# ASCII_09_FPGA_banks_5_6_7_8.net
KiCad netlist of a schematic drawn in Altium Designer
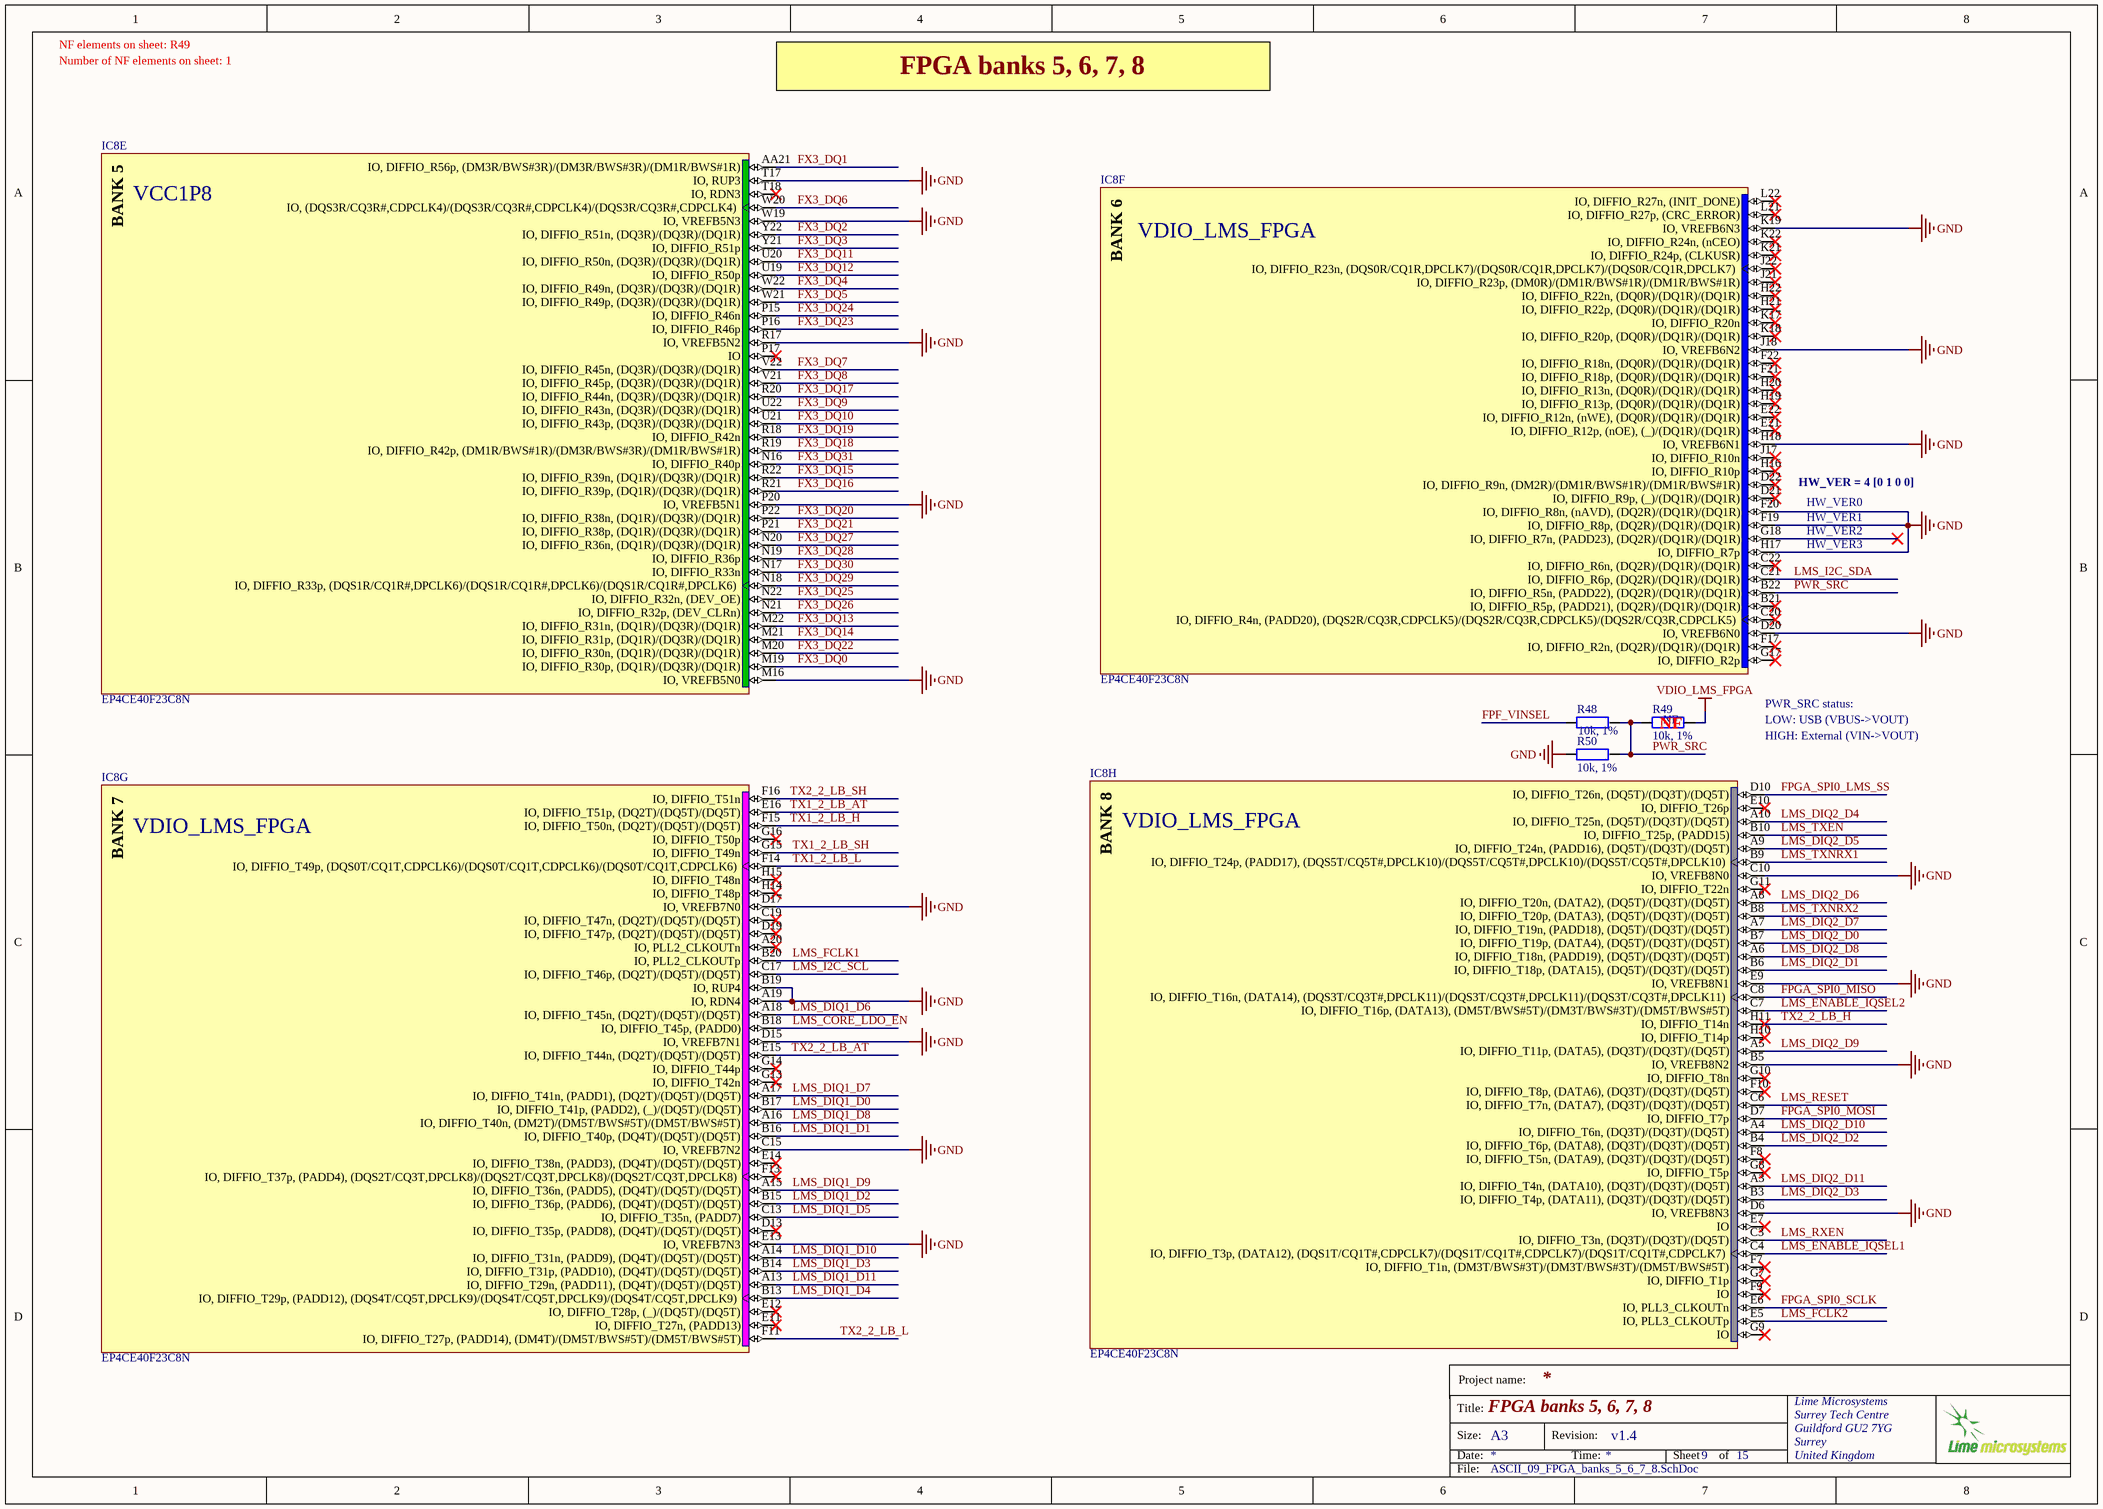
[diagram p0: ASCII_09_FPGA_banks_5_6_7_8.SchDoc]

(export (version "E")
  (design (tool "Eeschema 10.0.6"))
  (components
    (comp (ref "IC8")
      (value "EP4CE40F23C8N")
      (footprint "FBGA484_A-240")
      (description "IC FPGA 328 I/O 484FBGA")
      (fields (field (name "MANUFACTURER") "Altera"))
      (libsource (lib "LimeMicroAltiumLib_schLib") (part "EP4CE40F23C7N"))
    )
    (comp (ref "R48")
      (value "10k, 1%")
      (footprint "RES0402")
      (fields (field (name "MANUFACTURER") "Yageo") (field (name "TOLERANCE") "±1%"))
      (libsource (lib "LimeMicroAltiumLib_schLib") (part "Res_0402"))
    )
    (comp (ref "R49")
      (value "10k, 1%")
      (footprint "RES0402")
      (fields
        (field (name "ASSEMBLY INFO") "NF")
        (field (name "MANUFACTURER") "Yageo")
        (field (name "TOLERANCE") "±1%")
      )
      (libsource (lib "LimeMicroAltiumLib_schLib") (part "Res_0402"))
    )
    (comp (ref "R50")
      (value "10k, 1%")
      (footprint "RES0402")
      (fields (field (name "MANUFACTURER") "Yageo") (field (name "TOLERANCE") "±1%"))
      (libsource (lib "LimeMicroAltiumLib_schLib") (part "Res_0402"))
    )
  )
  (nets
    (net (code "1") (name "/FPF_VINSEL") (class "Default")
      (node (ref "R48") (pin "1") (pinfunction "1_1") (pintype "passive"))
    )
    (net (code "2") (name "/FPGA_SPI0_LMS_SS") (class "Default")
      (node (ref "IC8") (pin "D10") (pinfunction "IO,_DIFFIO_T26n,_(DQ5T)/(DQ3T)/(DQ5T)_D10") (pintype "bidirectional"))
    )
    (net (code "3") (name "/FPGA_SPI0_MISO") (class "Default")
      (node (ref "IC8") (pin "C8") (pinfunction "IO,_DIFFIO_T16n,_(DATA14),_(DQS3T/CQ3T#,DPCLK11)/(DQS3T/CQ3T#,DPCLK11)/(DQS3T/CQ3T#,DPCLK11)_C8") (pintype "bidirectional"))
    )
    (net (code "4") (name "/FPGA_SPI0_MOSI") (class "Default")
      (node (ref "IC8") (pin "D7") (pinfunction "IO,_DIFFIO_T7p_D7") (pintype "bidirectional"))
    )
    (net (code "5") (name "/FPGA_SPI0_SCLK") (class "Default")
      (node (ref "IC8") (pin "E6") (pinfunction "IO,_PLL3_CLKOUTn_E6") (pintype "bidirectional"))
    )
    (net (code "6") (name "/FX3_DQ0") (class "Default")
      (node (ref "IC8") (pin "M19") (pinfunction "IO,_DIFFIO_R30p,_(DQ1R)/(DQ3R)/(DQ1R)_M19") (pintype "bidirectional"))
    )
    (net (code "7") (name "/FX3_DQ1") (class "Default")
      (node (ref "IC8") (pin "AA21") (pinfunction "IO,_DIFFIO_R56p,_(DM3R/BWS#3R)/(DM3R/BWS#3R)/(DM1R/BWS#1R)_AA21") (pintype "bidirectional"))
    )
    (net (code "8") (name "/FX3_DQ2") (class "Default")
      (node (ref "IC8") (pin "Y22") (pinfunction "IO,_DIFFIO_R51n,_(DQ3R)/(DQ3R)/(DQ1R)_Y22") (pintype "bidirectional"))
    )
    (net (code "9") (name "/FX3_DQ3") (class "Default")
      (node (ref "IC8") (pin "Y21") (pinfunction "IO,_DIFFIO_R51p_Y21") (pintype "bidirectional"))
    )
    (net (code "10") (name "/FX3_DQ4") (class "Default")
      (node (ref "IC8") (pin "W22") (pinfunction "IO,_DIFFIO_R49n,_(DQ3R)/(DQ3R)/(DQ1R)_W22") (pintype "bidirectional"))
    )
    (net (code "11") (name "/FX3_DQ5") (class "Default")
      (node (ref "IC8") (pin "W21") (pinfunction "IO,_DIFFIO_R49p,_(DQ3R)/(DQ3R)/(DQ1R)_W21") (pintype "bidirectional"))
    )
    (net (code "12") (name "/FX3_DQ6") (class "Default")
      (node (ref "IC8") (pin "W20") (pinfunction "IO,_(DQS3R/CQ3R#,CDPCLK4)/(DQS3R/CQ3R#,CDPCLK4)/(DQS3R/CQ3R#,CDPCLK4)_W20") (pintype "bidirectional"))
    )
    (net (code "13") (name "/FX3_DQ7") (class "Default")
      (node (ref "IC8") (pin "V22") (pinfunction "IO,_DIFFIO_R45n,_(DQ3R)/(DQ3R)/(DQ1R)_V22") (pintype "bidirectional"))
    )
    (net (code "14") (name "/FX3_DQ8") (class "Default")
      (node (ref "IC8") (pin "V21") (pinfunction "IO,_DIFFIO_R45p,_(DQ3R)/(DQ3R)/(DQ1R)_V21") (pintype "bidirectional"))
    )
    (net (code "15") (name "/FX3_DQ9") (class "Default")
      (node (ref "IC8") (pin "U22") (pinfunction "IO,_DIFFIO_R43n,_(DQ3R)/(DQ3R)/(DQ1R)_U22") (pintype "bidirectional"))
    )
    (net (code "16") (name "/FX3_DQ10") (class "Default")
      (node (ref "IC8") (pin "U21") (pinfunction "IO,_DIFFIO_R43p,_(DQ3R)/(DQ3R)/(DQ1R)_U21") (pintype "bidirectional"))
    )
    (net (code "17") (name "/FX3_DQ11") (class "Default")
      (node (ref "IC8") (pin "U20") (pinfunction "IO,_DIFFIO_R50n,_(DQ3R)/(DQ3R)/(DQ1R)_U20") (pintype "bidirectional"))
    )
    (net (code "18") (name "/FX3_DQ12") (class "Default")
      (node (ref "IC8") (pin "U19") (pinfunction "IO,_DIFFIO_R50p_U19") (pintype "bidirectional"))
    )
    (net (code "19") (name "/FX3_DQ13") (class "Default")
      (node (ref "IC8") (pin "M22") (pinfunction "IO,_DIFFIO_R31n,_(DQ1R)/(DQ3R)/(DQ1R)_M22") (pintype "bidirectional"))
    )
    (net (code "20") (name "/FX3_DQ14") (class "Default")
      (node (ref "IC8") (pin "M21") (pinfunction "IO,_DIFFIO_R31p,_(DQ1R)/(DQ3R)/(DQ1R)_M21") (pintype "bidirectional"))
    )
    (net (code "21") (name "/FX3_DQ15") (class "Default")
      (node (ref "IC8") (pin "R22") (pinfunction "IO,_DIFFIO_R39n,_(DQ1R)/(DQ3R)/(DQ1R)_R22") (pintype "bidirectional"))
    )
    (net (code "22") (name "/FX3_DQ16") (class "Default")
      (node (ref "IC8") (pin "R21") (pinfunction "IO,_DIFFIO_R39p,_(DQ1R)/(DQ3R)/(DQ1R)_R21") (pintype "bidirectional"))
    )
    (net (code "23") (name "/FX3_DQ17") (class "Default")
      (node (ref "IC8") (pin "R20") (pinfunction "IO,_DIFFIO_R44n,_(DQ3R)/(DQ3R)/(DQ1R)_R20") (pintype "bidirectional"))
    )
    (net (code "24") (name "/FX3_DQ18") (class "Default")
      (node (ref "IC8") (pin "R19") (pinfunction "IO,_DIFFIO_R42p,_(DM1R/BWS#1R)/(DM3R/BWS#3R)/(DM1R/BWS#1R)_R19") (pintype "bidirectional"))
    )
    (net (code "25") (name "/FX3_DQ19") (class "Default")
      (node (ref "IC8") (pin "R18") (pinfunction "IO,_DIFFIO_R42n_R18") (pintype "bidirectional"))
    )
    (net (code "26") (name "/FX3_DQ20") (class "Default")
      (node (ref "IC8") (pin "P22") (pinfunction "IO,_DIFFIO_R38n,_(DQ1R)/(DQ3R)/(DQ1R)_P22") (pintype "bidirectional"))
    )
    (net (code "27") (name "/FX3_DQ21") (class "Default")
      (node (ref "IC8") (pin "P21") (pinfunction "IO,_DIFFIO_R38p,_(DQ1R)/(DQ3R)/(DQ1R)_P21") (pintype "bidirectional"))
    )
    (net (code "28") (name "/FX3_DQ22") (class "Default")
      (node (ref "IC8") (pin "M20") (pinfunction "IO,_DIFFIO_R30n,_(DQ1R)/(DQ3R)/(DQ1R)_M20") (pintype "bidirectional"))
    )
    (net (code "29") (name "/FX3_DQ23") (class "Default")
      (node (ref "IC8") (pin "P16") (pinfunction "IO,_DIFFIO_R46p_P16") (pintype "bidirectional"))
    )
    (net (code "30") (name "/FX3_DQ24") (class "Default")
      (node (ref "IC8") (pin "P15") (pinfunction "IO,_DIFFIO_R46n_P15") (pintype "bidirectional"))
    )
    (net (code "31") (name "/FX3_DQ25") (class "Default")
      (node (ref "IC8") (pin "N22") (pinfunction "IO,_DIFFIO_R32n,_(DEV_OE)_N22") (pintype "bidirectional"))
    )
    (net (code "32") (name "/FX3_DQ26") (class "Default")
      (node (ref "IC8") (pin "N21") (pinfunction "IO,_DIFFIO_R32p,_(DEV_CLRn)_N21") (pintype "bidirectional"))
    )
    (net (code "33") (name "/FX3_DQ27") (class "Default")
      (node (ref "IC8") (pin "N20") (pinfunction "IO,_DIFFIO_R36n,_(DQ1R)/(DQ3R)/(DQ1R)_N20") (pintype "bidirectional"))
    )
    (net (code "34") (name "/FX3_DQ28") (class "Default")
      (node (ref "IC8") (pin "N19") (pinfunction "IO,_DIFFIO_R36p_N19") (pintype "bidirectional"))
    )
    (net (code "35") (name "/FX3_DQ29") (class "Default")
      (node (ref "IC8") (pin "N18") (pinfunction "IO,_DIFFIO_R33p,_(DQS1R/CQ1R#,DPCLK6)/(DQS1R/CQ1R#,DPCLK6)/(DQS1R/CQ1R#,DPCLK6)_N18") (pintype "bidirectional"))
    )
    (net (code "36") (name "/FX3_DQ30") (class "Default")
      (node (ref "IC8") (pin "N17") (pinfunction "IO,_DIFFIO_R33n_N17") (pintype "bidirectional"))
    )
    (net (code "37") (name "/FX3_DQ31") (class "Default")
      (node (ref "IC8") (pin "N16") (pinfunction "IO,_DIFFIO_R40p_N16") (pintype "bidirectional"))
    )
    (net (code "38") (name "/LMS_CORE_LDO_EN") (class "Default")
      (node (ref "IC8") (pin "B18") (pinfunction "IO,_DIFFIO_T45p,_(PADD0)_B18") (pintype "bidirectional"))
    )
    (net (code "39") (name "/LMS_DIQ1_D0") (class "Default")
      (node (ref "IC8") (pin "B17") (pinfunction "IO,_DIFFIO_T41p,_(PADD2),_(_)/(DQ5T)/(DQ5T)_B17") (pintype "bidirectional"))
    )
    (net (code "40") (name "/LMS_DIQ1_D1") (class "Default")
      (node (ref "IC8") (pin "B16") (pinfunction "IO,_DIFFIO_T40p,_(DQ4T)/(DQ5T)/(DQ5T)_B16") (pintype "bidirectional"))
    )
    (net (code "41") (name "/LMS_DIQ1_D2") (class "Default")
      (node (ref "IC8") (pin "B15") (pinfunction "IO,_DIFFIO_T36p,_(PADD6),_(DQ4T)/(DQ5T)/(DQ5T)_B15") (pintype "bidirectional"))
    )
    (net (code "42") (name "/LMS_DIQ1_D3") (class "Default")
      (node (ref "IC8") (pin "B14") (pinfunction "IO,_DIFFIO_T31p,_(PADD10),_(DQ4T)/(DQ5T)/(DQ5T)_B14") (pintype "bidirectional"))
    )
    (net (code "43") (name "/LMS_DIQ1_D4") (class "Default")
      (node (ref "IC8") (pin "B13") (pinfunction "IO,_DIFFIO_T29p,_(PADD12),_(DQS4T/CQ5T,DPCLK9)/(DQS4T/CQ5T,DPCLK9)/(DQS4T/CQ5T,DPCLK9)_B13") (pintype "bidirectional"))
    )
    (net (code "44") (name "/LMS_DIQ1_D5") (class "Default")
      (node (ref "IC8") (pin "C13") (pinfunction "IO,_DIFFIO_T35n,_(PADD7)_C13") (pintype "bidirectional"))
    )
    (net (code "45") (name "/LMS_DIQ1_D6") (class "Default")
      (node (ref "IC8") (pin "A18") (pinfunction "IO,_DIFFIO_T45n,_(DQ2T)/(DQ5T)/(DQ5T)_A18") (pintype "bidirectional"))
    )
    (net (code "46") (name "/LMS_DIQ1_D7") (class "Default")
      (node (ref "IC8") (pin "A17") (pinfunction "IO,_DIFFIO_T41n,_(PADD1),_(DQ2T)/(DQ5T)/(DQ5T)_A17") (pintype "bidirectional"))
    )
    (net (code "47") (name "/LMS_DIQ1_D8") (class "Default")
      (node (ref "IC8") (pin "A16") (pinfunction "IO,_DIFFIO_T40n,_(DM2T)/(DM5T/BWS#5T)/(DM5T/BWS#5T)_A16") (pintype "bidirectional"))
    )
    (net (code "48") (name "/LMS_DIQ1_D9") (class "Default")
      (node (ref "IC8") (pin "A15") (pinfunction "IO,_DIFFIO_T36n,_(PADD5),_(DQ4T)/(DQ5T)/(DQ5T)_A15") (pintype "bidirectional"))
    )
    (net (code "49") (name "/LMS_DIQ1_D10") (class "Default")
      (node (ref "IC8") (pin "A14") (pinfunction "IO,_DIFFIO_T31n,_(PADD9),_(DQ4T)/(DQ5T)/(DQ5T)_A14") (pintype "bidirectional"))
    )
    (net (code "50") (name "/LMS_DIQ1_D11") (class "Default")
      (node (ref "IC8") (pin "A13") (pinfunction "IO,_DIFFIO_T29n,_(PADD11),_(DQ4T)/(DQ5T)/(DQ5T)_A13") (pintype "bidirectional"))
    )
    (net (code "51") (name "/LMS_DIQ2_D0") (class "Default")
      (node (ref "IC8") (pin "B7") (pinfunction "IO,_DIFFIO_T19p,_(DATA4),_(DQ5T)/(DQ3T)/(DQ5T)_B7") (pintype "bidirectional"))
    )
    (net (code "52") (name "/LMS_DIQ2_D1") (class "Default")
      (node (ref "IC8") (pin "B6") (pinfunction "IO,_DIFFIO_T18p,_(DATA15),_(DQ5T)/(DQ3T)/(DQ5T)_B6") (pintype "bidirectional"))
    )
    (net (code "53") (name "/LMS_DIQ2_D2") (class "Default")
      (node (ref "IC8") (pin "B4") (pinfunction "IO,_DIFFIO_T6p,_(DATA8),_(DQ3T)/(DQ3T)/(DQ5T)_B4") (pintype "bidirectional"))
    )
    (net (code "54") (name "/LMS_DIQ2_D3") (class "Default")
      (node (ref "IC8") (pin "B3") (pinfunction "IO,_DIFFIO_T4p,_(DATA11),_(DQ3T)/(DQ3T)/(DQ5T)_B3") (pintype "bidirectional"))
    )
    (net (code "55") (name "/LMS_DIQ2_D4") (class "Default")
      (node (ref "IC8") (pin "A10") (pinfunction "IO,_DIFFIO_T25n,_(DQ5T)/(DQ3T)/(DQ5T)_A10") (pintype "bidirectional"))
    )
    (net (code "56") (name "/LMS_DIQ2_D5") (class "Default")
      (node (ref "IC8") (pin "A9") (pinfunction "IO,_DIFFIO_T24n,_(PADD16),_(DQ5T)/(DQ3T)/(DQ5T)_A9") (pintype "bidirectional"))
    )
    (net (code "57") (name "/LMS_DIQ2_D6") (class "Default")
      (node (ref "IC8") (pin "A8") (pinfunction "IO,_DIFFIO_T20n,_(DATA2),_(DQ5T)/(DQ3T)/(DQ5T)_A8") (pintype "bidirectional"))
    )
    (net (code "58") (name "/LMS_DIQ2_D7") (class "Default")
      (node (ref "IC8") (pin "A7") (pinfunction "IO,_DIFFIO_T19n,_(PADD18),_(DQ5T)/(DQ3T)/(DQ5T)_A7") (pintype "bidirectional"))
    )
    (net (code "59") (name "/LMS_DIQ2_D8") (class "Default")
      (node (ref "IC8") (pin "A6") (pinfunction "IO,_DIFFIO_T18n,_(PADD19),_(DQ5T)/(DQ3T)/(DQ5T)_A6") (pintype "bidirectional"))
    )
    (net (code "60") (name "/LMS_DIQ2_D9") (class "Default")
      (node (ref "IC8") (pin "A5") (pinfunction "IO,_DIFFIO_T11p,_(DATA5),_(DQ3T)/(DQ3T)/(DQ5T)_A5") (pintype "bidirectional"))
    )
    (net (code "61") (name "/LMS_DIQ2_D10") (class "Default")
      (node (ref "IC8") (pin "A4") (pinfunction "IO,_DIFFIO_T6n,_(DQ3T)/(DQ3T)/(DQ5T)_A4") (pintype "bidirectional"))
    )
    (net (code "62") (name "/LMS_DIQ2_D11") (class "Default")
      (node (ref "IC8") (pin "A3") (pinfunction "IO,_DIFFIO_T4n,_(DATA10),_(DQ3T)/(DQ3T)/(DQ5T)_A3") (pintype "bidirectional"))
    )
    (net (code "63") (name "/LMS_ENABLE_IQSEL1") (class "Default")
      (node (ref "IC8") (pin "C4") (pinfunction "IO,_DIFFIO_T3p,_(DATA12),_(DQS1T/CQ1T#,CDPCLK7)/(DQS1T/CQ1T#,CDPCLK7)/(DQS1T/CQ1T#,CDPCLK7)_C4") (pintype "bidirectional"))
    )
    (net (code "64") (name "/LMS_ENABLE_IQSEL2") (class "Default")
      (node (ref "IC8") (pin "C7") (pinfunction "IO,_DIFFIO_T16p,_(DATA13),_(DM5T/BWS#5T)/(DM3T/BWS#3T)/(DM5T/BWS#5T)_C7") (pintype "bidirectional"))
    )
    (net (code "65") (name "/LMS_FCLK1") (class "Default")
      (node (ref "IC8") (pin "B20") (pinfunction "IO,_PLL2_CLKOUTp_B20") (pintype "bidirectional"))
    )
    (net (code "66") (name "/LMS_FCLK2") (class "Default")
      (node (ref "IC8") (pin "E5") (pinfunction "IO,_PLL3_CLKOUTp_E5") (pintype "bidirectional"))
    )
    (net (code "67") (name "/LMS_I2C_SCL") (class "Default")
      (node (ref "IC8") (pin "C17") (pinfunction "IO,_DIFFIO_T46p,_(DQ2T)/(DQ5T)/(DQ5T)_C17") (pintype "bidirectional"))
    )
    (net (code "68") (name "/LMS_I2C_SDA") (class "Default")
      (node (ref "IC8") (pin "C21") (pinfunction "IO,_DIFFIO_R6p,_(DQ2R)/(DQ1R)/(DQ1R)_C21") (pintype "bidirectional"))
    )
    (net (code "69") (name "/LMS_RESET") (class "Default")
      (node (ref "IC8") (pin "C6") (pinfunction "IO,_DIFFIO_T7n,_(DATA7),_(DQ3T)/(DQ3T)/(DQ5T)_C6") (pintype "bidirectional"))
    )
    (net (code "70") (name "/LMS_RXEN") (class "Default")
      (node (ref "IC8") (pin "C3") (pinfunction "IO,_DIFFIO_T3n,_(DQ3T)/(DQ3T)/(DQ5T)_C3") (pintype "bidirectional"))
    )
    (net (code "71") (name "/LMS_TXEN") (class "Default")
      (node (ref "IC8") (pin "B10") (pinfunction "IO,_DIFFIO_T25p,_(PADD15)_B10") (pintype "bidirectional"))
    )
    (net (code "72") (name "/LMS_TXNRX1") (class "Default")
      (node (ref "IC8") (pin "B9") (pinfunction "IO,_DIFFIO_T24p,_(PADD17),_(DQS5T/CQ5T#,DPCLK10)/(DQS5T/CQ5T#,DPCLK10)/(DQS5T/CQ5T#,DPCLK10)_B9") (pintype "bidirectional"))
    )
    (net (code "73") (name "/LMS_TXNRX2") (class "Default")
      (node (ref "IC8") (pin "B8") (pinfunction "IO,_DIFFIO_T20p,_(DATA3),_(DQ5T)/(DQ3T)/(DQ5T)_B8") (pintype "bidirectional"))
    )
    (net (code "74") (name "/PWR_SRC") (class "Default")
      (node (ref "IC8") (pin "B22") (pinfunction "IO,_DIFFIO_R5n,_(PADD22),_(DQ2R)/(DQ1R)/(DQ1R)_B22") (pintype "bidirectional"))
      (node (ref "R48") (pin "2") (pinfunction "2_2") (pintype "passive"))
      (node (ref "R49") (pin "1") (pinfunction "1_1") (pintype "passive"))
      (node (ref "R50") (pin "2") (pinfunction "2_2") (pintype "passive"))
    )
    (net (code "75") (name "/TX1_2_LB_AT") (class "Default")
      (node (ref "IC8") (pin "E16") (pinfunction "IO,_DIFFIO_T51p,_(DQ2T)/(DQ5T)/(DQ5T)_E16") (pintype "bidirectional"))
    )
    (net (code "76") (name "/TX1_2_LB_H") (class "Default")
      (node (ref "IC8") (pin "F15") (pinfunction "IO,_DIFFIO_T50n,_(DQ2T)/(DQ5T)/(DQ5T)_F15") (pintype "bidirectional"))
    )
    (net (code "77") (name "/TX1_2_LB_L") (class "Default")
      (node (ref "IC8") (pin "F14") (pinfunction "IO,_DIFFIO_T49p,_(DQS0T/CQ1T,CDPCLK6)/(DQS0T/CQ1T,CDPCLK6)/(DQS0T/CQ1T,CDPCLK6)_F14") (pintype "bidirectional"))
    )
    (net (code "78") (name "/TX1_2_LB_SH") (class "Default")
      (node (ref "IC8") (pin "G15") (pinfunction "IO,_DIFFIO_T49n_G15") (pintype "bidirectional"))
    )
    (net (code "79") (name "/TX2_2_LB_AT") (class "Default")
      (node (ref "IC8") (pin "E15") (pinfunction "IO,_DIFFIO_T44n,_(DQ2T)/(DQ5T)/(DQ5T)_E15") (pintype "bidirectional"))
    )
    (net (code "80") (name "/TX2_2_LB_H") (class "Default")
      (node (ref "IC8") (pin "H11") (pinfunction "IO,_DIFFIO_T14n_H11") (pintype "bidirectional+no_connect"))
    )
    (net (code "81") (name "/TX2_2_LB_L") (class "Default")
      (node (ref "IC8") (pin "F11") (pinfunction "IO,_DIFFIO_T27p,_(PADD14),_(DM4T)/(DM5T/BWS#5T)/(DM5T/BWS#5T)_F11") (pintype "bidirectional"))
    )
    (net (code "82") (name "/TX2_2_LB_SH") (class "Default")
      (node (ref "IC8") (pin "F16") (pinfunction "IO,_DIFFIO_T51n_F16") (pintype "bidirectional"))
    )
    (net (code "83") (name "GND") (class "Default")
      (node (ref "IC8") (pin "A19") (pinfunction "IO,_RDN4_A19") (pintype "bidirectional"))
      (node (ref "IC8") (pin "B19") (pinfunction "IO,_RUP4_B19") (pintype "bidirectional"))
      (node (ref "IC8") (pin "B5") (pinfunction "IO,_VREFB8N2_B5") (pintype "bidirectional"))
      (node (ref "IC8") (pin "C10") (pinfunction "IO,_VREFB8N0_C10") (pintype "bidirectional"))
      (node (ref "IC8") (pin "C15") (pinfunction "IO,_VREFB7N2_C15") (pintype "bidirectional"))
      (node (ref "IC8") (pin "D15") (pinfunction "IO,_VREFB7N1_D15") (pintype "bidirectional"))
      (node (ref "IC8") (pin "D17") (pinfunction "IO,_VREFB7N0_D17") (pintype "bidirectional"))
      (node (ref "IC8") (pin "D20") (pinfunction "IO,_VREFB6N0_D20") (pintype "bidirectional"))
      (node (ref "IC8") (pin "D6") (pinfunction "IO,_VREFB8N3_D6") (pintype "bidirectional"))
      (node (ref "IC8") (pin "E13") (pinfunction "IO,_VREFB7N3_E13") (pintype "bidirectional"))
      (node (ref "IC8") (pin "E9") (pinfunction "IO,_VREFB8N1_E9") (pintype "bidirectional"))
      (node (ref "IC8") (pin "F19") (pinfunction "IO,_DIFFIO_R8p,_(DQ2R)/(DQ1R)/(DQ1R)_F19") (pintype "bidirectional"))
      (node (ref "IC8") (pin "F20") (pinfunction "IO,_DIFFIO_R8n,_(nAVD),_(DQ2R)/(DQ1R)/(DQ1R)_F20") (pintype "bidirectional"))
      (node (ref "IC8") (pin "H17") (pinfunction "IO,_DIFFIO_R7p_H17") (pintype "bidirectional"))
      (node (ref "IC8") (pin "H18") (pinfunction "IO,_VREFB6N1_H18") (pintype "bidirectional"))
      (node (ref "IC8") (pin "J18") (pinfunction "IO,_VREFB6N2_J18") (pintype "bidirectional"))
      (node (ref "IC8") (pin "K19") (pinfunction "IO,_VREFB6N3_K19") (pintype "bidirectional"))
      (node (ref "IC8") (pin "M16") (pinfunction "IO,_VREFB5N0_M16") (pintype "bidirectional"))
      (node (ref "IC8") (pin "P20") (pinfunction "IO,_VREFB5N1_P20") (pintype "bidirectional"))
      (node (ref "IC8") (pin "R17") (pinfunction "IO,_VREFB5N2_R17") (pintype "bidirectional"))
      (node (ref "IC8") (pin "T17") (pinfunction "IO,_RUP3_T17") (pintype "bidirectional"))
      (node (ref "IC8") (pin "W19") (pinfunction "IO,_VREFB5N3_W19") (pintype "bidirectional"))
      (node (ref "R50") (pin "1") (pinfunction "1_1") (pintype "passive"))
    )
    (net (code "84") (name "VDIO_LMS_FPGA") (class "Default")
      (node (ref "R49") (pin "2") (pinfunction "2_2") (pintype "passive"))
    )
    (net (code "85") (name "unconnected-(IC8E-IO,_RDN3-PadT18)") (class "Default")
      (node (ref "IC8") (pin "T18") (pinfunction "IO,_RDN3_T18") (pintype "bidirectional+no_connect"))
    )
    (net (code "86") (name "unconnected-(IC8E-IO-PadP17)") (class "Default")
      (node (ref "IC8") (pin "P17") (pinfunction "IO_P17") (pintype "bidirectional+no_connect"))
    )
    (net (code "87") (name "unconnected-(IC8F-IO,_DIFFIO_R2n,_(DQ2R){slash}(DQ1R){slash}(DQ1R)-PadF17)") (class "Default")
      (node (ref "IC8") (pin "F17") (pinfunction "IO,_DIFFIO_R2n,_(DQ2R)/(DQ1R)/(DQ1R)_F17") (pintype "bidirectional+no_connect"))
    )
    (net (code "88") (name "unconnected-(IC8F-IO,_DIFFIO_R2p-PadG17)") (class "Default")
      (node (ref "IC8") (pin "G17") (pinfunction "IO,_DIFFIO_R2p_G17") (pintype "bidirectional+no_connect"))
    )
    (net (code "89") (name "unconnected-(IC8F-IO,_DIFFIO_R4n,_(PADD20),_(DQS2R{slash}CQ3R,CDPCLK5){slash}(DQS2R{slash}CQ3R,CDPCLK5){slash}(DQS2R{slash}CQ3R,CDPCLK5)-PadC20)") (class "Default")
      (node (ref "IC8") (pin "C20") (pinfunction "IO,_DIFFIO_R4n,_(PADD20),_(DQS2R/CQ3R,CDPCLK5)/(DQS2R/CQ3R,CDPCLK5)/(DQS2R/CQ3R,CDPCLK5)_C20") (pintype "bidirectional+no_connect"))
    )
    (net (code "90") (name "unconnected-(IC8F-IO,_DIFFIO_R5p,_(PADD21),_(DQ2R){slash}(DQ1R){slash}(DQ1R)-PadB21)") (class "Default")
      (node (ref "IC8") (pin "B21") (pinfunction "IO,_DIFFIO_R5p,_(PADD21),_(DQ2R)/(DQ1R)/(DQ1R)_B21") (pintype "bidirectional+no_connect"))
    )
    (net (code "91") (name "unconnected-(IC8F-IO,_DIFFIO_R6n,_(DQ2R){slash}(DQ1R){slash}(DQ1R)-PadC22)") (class "Default")
      (node (ref "IC8") (pin "C22") (pinfunction "IO,_DIFFIO_R6n,_(DQ2R)/(DQ1R)/(DQ1R)_C22") (pintype "bidirectional+no_connect"))
    )
    (net (code "92") (name "unconnected-(IC8F-IO,_DIFFIO_R7n,_(PADD23),_(DQ2R){slash}(DQ1R){slash}(DQ1R)-PadG18)") (class "Default")
      (node (ref "IC8") (pin "G18") (pinfunction "IO,_DIFFIO_R7n,_(PADD23),_(DQ2R)/(DQ1R)/(DQ1R)_G18") (pintype "bidirectional+no_connect"))
    )
    (net (code "93") (name "unconnected-(IC8F-IO,_DIFFIO_R9n,_(DM2R){slash}(DM1R{slash}BWS#1R){slash}(DM1R{slash}BWS#1R)-PadD22)") (class "Default")
      (node (ref "IC8") (pin "D22") (pinfunction "IO,_DIFFIO_R9n,_(DM2R)/(DM1R/BWS#1R)/(DM1R/BWS#1R)_D22") (pintype "bidirectional+no_connect"))
    )
    (net (code "94") (name "unconnected-(IC8F-IO,_DIFFIO_R9p,_(_){slash}(DQ1R){slash}(DQ1R)-PadD21)") (class "Default")
      (node (ref "IC8") (pin "D21") (pinfunction "IO,_DIFFIO_R9p,_(_)/(DQ1R)/(DQ1R)_D21") (pintype "bidirectional+no_connect"))
    )
    (net (code "95") (name "unconnected-(IC8F-IO,_DIFFIO_R10n-PadJ17)") (class "Default")
      (node (ref "IC8") (pin "J17") (pinfunction "IO,_DIFFIO_R10n_J17") (pintype "bidirectional+no_connect"))
    )
    (net (code "96") (name "unconnected-(IC8F-IO,_DIFFIO_R10p-PadH16)") (class "Default")
      (node (ref "IC8") (pin "H16") (pinfunction "IO,_DIFFIO_R10p_H16") (pintype "bidirectional+no_connect"))
    )
    (net (code "97") (name "unconnected-(IC8F-IO,_DIFFIO_R12n,_(nWE),_(DQ0R){slash}(DQ1R){slash}(DQ1R)-PadE22)") (class "Default")
      (node (ref "IC8") (pin "E22") (pinfunction "IO,_DIFFIO_R12n,_(nWE),_(DQ0R)/(DQ1R)/(DQ1R)_E22") (pintype "bidirectional+no_connect"))
    )
    (net (code "98") (name "unconnected-(IC8F-IO,_DIFFIO_R12p,_(nOE),_(_){slash}(DQ1R){slash}(DQ1R)-PadE21)") (class "Default")
      (node (ref "IC8") (pin "E21") (pinfunction "IO,_DIFFIO_R12p,_(nOE),_(_)/(DQ1R)/(DQ1R)_E21") (pintype "bidirectional+no_connect"))
    )
    (net (code "99") (name "unconnected-(IC8F-IO,_DIFFIO_R13n,_(DQ0R){slash}(DQ1R){slash}(DQ1R)-PadH20)") (class "Default")
      (node (ref "IC8") (pin "H20") (pinfunction "IO,_DIFFIO_R13n,_(DQ0R)/(DQ1R)/(DQ1R)_H20") (pintype "bidirectional+no_connect"))
    )
    (net (code "100") (name "unconnected-(IC8F-IO,_DIFFIO_R13p,_(DQ0R){slash}(DQ1R){slash}(DQ1R)-PadH19)") (class "Default")
      (node (ref "IC8") (pin "H19") (pinfunction "IO,_DIFFIO_R13p,_(DQ0R)/(DQ1R)/(DQ1R)_H19") (pintype "bidirectional+no_connect"))
    )
    (net (code "101") (name "unconnected-(IC8F-IO,_DIFFIO_R18n,_(DQ0R){slash}(DQ1R){slash}(DQ1R)-PadF22)") (class "Default")
      (node (ref "IC8") (pin "F22") (pinfunction "IO,_DIFFIO_R18n,_(DQ0R)/(DQ1R)/(DQ1R)_F22") (pintype "bidirectional+no_connect"))
    )
    (net (code "102") (name "unconnected-(IC8F-IO,_DIFFIO_R18p,_(DQ0R){slash}(DQ1R){slash}(DQ1R)-PadF21)") (class "Default")
      (node (ref "IC8") (pin "F21") (pinfunction "IO,_DIFFIO_R18p,_(DQ0R)/(DQ1R)/(DQ1R)_F21") (pintype "bidirectional+no_connect"))
    )
    (net (code "103") (name "unconnected-(IC8F-IO,_DIFFIO_R20n-PadK17)") (class "Default")
      (node (ref "IC8") (pin "K17") (pinfunction "IO,_DIFFIO_R20n_K17") (pintype "bidirectional+no_connect"))
    )
    (net (code "104") (name "unconnected-(IC8F-IO,_DIFFIO_R20p,_(DQ0R){slash}(DQ1R){slash}(DQ1R)-PadK18)") (class "Default")
      (node (ref "IC8") (pin "K18") (pinfunction "IO,_DIFFIO_R20p,_(DQ0R)/(DQ1R)/(DQ1R)_K18") (pintype "bidirectional+no_connect"))
    )
    (net (code "105") (name "unconnected-(IC8F-IO,_DIFFIO_R22n,_(DQ0R){slash}(DQ1R){slash}(DQ1R)-PadH22)") (class "Default")
      (node (ref "IC8") (pin "H22") (pinfunction "IO,_DIFFIO_R22n,_(DQ0R)/(DQ1R)/(DQ1R)_H22") (pintype "bidirectional+no_connect"))
    )
    (net (code "106") (name "unconnected-(IC8F-IO,_DIFFIO_R22p,_(DQ0R){slash}(DQ1R){slash}(DQ1R)-PadH21)") (class "Default")
      (node (ref "IC8") (pin "H21") (pinfunction "IO,_DIFFIO_R22p,_(DQ0R)/(DQ1R)/(DQ1R)_H21") (pintype "bidirectional+no_connect"))
    )
    (net (code "107") (name "unconnected-(IC8F-IO,_DIFFIO_R23n,_(DQS0R{slash}CQ1R,DPCLK7){slash}(DQS0R{slash}CQ1R,DPCLK7){slash}(DQS0R{slash}CQ1R,DPCLK7)-PadJ22)") (class "Default")
      (node (ref "IC8") (pin "J22") (pinfunction "IO,_DIFFIO_R23n,_(DQS0R/CQ1R,DPCLK7)/(DQS0R/CQ1R,DPCLK7)/(DQS0R/CQ1R,DPCLK7)_J22") (pintype "bidirectional+no_connect"))
    )
    (net (code "108") (name "unconnected-(IC8F-IO,_DIFFIO_R23p,_(DM0R){slash}(DM1R{slash}BWS#1R){slash}(DM1R{slash}BWS#1R)-PadJ21)") (class "Default")
      (node (ref "IC8") (pin "J21") (pinfunction "IO,_DIFFIO_R23p,_(DM0R)/(DM1R/BWS#1R)/(DM1R/BWS#1R)_J21") (pintype "bidirectional+no_connect"))
    )
    (net (code "109") (name "unconnected-(IC8F-IO,_DIFFIO_R24n,_(nCEO)-PadK22)") (class "Default")
      (node (ref "IC8") (pin "K22") (pinfunction "IO,_DIFFIO_R24n,_(nCEO)_K22") (pintype "bidirectional+no_connect"))
    )
    (net (code "110") (name "unconnected-(IC8F-IO,_DIFFIO_R24p,_(CLKUSR)-PadK21)") (class "Default")
      (node (ref "IC8") (pin "K21") (pinfunction "IO,_DIFFIO_R24p,_(CLKUSR)_K21") (pintype "bidirectional+no_connect"))
    )
    (net (code "111") (name "unconnected-(IC8F-IO,_DIFFIO_R27n,_(INIT_DONE)-PadL22)") (class "Default")
      (node (ref "IC8") (pin "L22") (pinfunction "IO,_DIFFIO_R27n,_(INIT_DONE)_L22") (pintype "bidirectional+no_connect"))
    )
    (net (code "112") (name "unconnected-(IC8F-IO,_DIFFIO_R27p,_(CRC_ERROR)-PadL21)") (class "Default")
      (node (ref "IC8") (pin "L21") (pinfunction "IO,_DIFFIO_R27p,_(CRC_ERROR)_L21") (pintype "bidirectional+no_connect"))
    )
    (net (code "113") (name "unconnected-(IC8G-IO,_DIFFIO_T27n,_(PADD13)-PadE11)") (class "Default")
      (node (ref "IC8") (pin "E11") (pinfunction "IO,_DIFFIO_T27n,_(PADD13)_E11") (pintype "bidirectional+no_connect"))
    )
    (net (code "114") (name "unconnected-(IC8G-IO,_DIFFIO_T28p,_(_){slash}(DQ5T){slash}(DQ5T)-PadE12)") (class "Default")
      (node (ref "IC8") (pin "E12") (pinfunction "IO,_DIFFIO_T28p,_(_)/(DQ5T)/(DQ5T)_E12") (pintype "bidirectional+no_connect"))
    )
    (net (code "115") (name "unconnected-(IC8G-IO,_DIFFIO_T35p,_(PADD8),_(DQ4T){slash}(DQ5T){slash}(DQ5T)-PadD13)") (class "Default")
      (node (ref "IC8") (pin "D13") (pinfunction "IO,_DIFFIO_T35p,_(PADD8),_(DQ4T)/(DQ5T)/(DQ5T)_D13") (pintype "bidirectional+no_connect"))
    )
    (net (code "116") (name "unconnected-(IC8G-IO,_DIFFIO_T37p,_(PADD4),_(DQS2T{slash}CQ3T,DPCLK8){slash}(DQS2T{slash}CQ3T,DPCLK8){slash}(DQS2T{slash}CQ3T,DPCLK8)-PadF13)") (class "Default")
      (node (ref "IC8") (pin "F13") (pinfunction "IO,_DIFFIO_T37p,_(PADD4),_(DQS2T/CQ3T,DPCLK8)/(DQS2T/CQ3T,DPCLK8)/(DQS2T/CQ3T,DPCLK8)_F13") (pintype "bidirectional+no_connect"))
    )
    (net (code "117") (name "unconnected-(IC8G-IO,_DIFFIO_T38n,_(PADD3),_(DQ4T){slash}(DQ5T){slash}(DQ5T)-PadE14)") (class "Default")
      (node (ref "IC8") (pin "E14") (pinfunction "IO,_DIFFIO_T38n,_(PADD3),_(DQ4T)/(DQ5T)/(DQ5T)_E14") (pintype "bidirectional+no_connect"))
    )
    (net (code "118") (name "unconnected-(IC8G-IO,_DIFFIO_T42n-PadG13)") (class "Default")
      (node (ref "IC8") (pin "G13") (pinfunction "IO,_DIFFIO_T42n_G13") (pintype "bidirectional+no_connect"))
    )
    (net (code "119") (name "unconnected-(IC8G-IO,_DIFFIO_T44p-PadG14)") (class "Default")
      (node (ref "IC8") (pin "G14") (pinfunction "IO,_DIFFIO_T44p_G14") (pintype "bidirectional+no_connect"))
    )
    (net (code "120") (name "unconnected-(IC8G-IO,_DIFFIO_T47n,_(DQ2T){slash}(DQ5T){slash}(DQ5T)-PadC19)") (class "Default")
      (node (ref "IC8") (pin "C19") (pinfunction "IO,_DIFFIO_T47n,_(DQ2T)/(DQ5T)/(DQ5T)_C19") (pintype "bidirectional+no_connect"))
    )
    (net (code "121") (name "unconnected-(IC8G-IO,_DIFFIO_T47p,_(DQ2T){slash}(DQ5T){slash}(DQ5T)-PadD19)") (class "Default")
      (node (ref "IC8") (pin "D19") (pinfunction "IO,_DIFFIO_T47p,_(DQ2T)/(DQ5T)/(DQ5T)_D19") (pintype "bidirectional+no_connect"))
    )
    (net (code "122") (name "unconnected-(IC8G-IO,_DIFFIO_T48n-PadH15)") (class "Default")
      (node (ref "IC8") (pin "H15") (pinfunction "IO,_DIFFIO_T48n_H15") (pintype "bidirectional+no_connect"))
    )
    (net (code "123") (name "unconnected-(IC8G-IO,_DIFFIO_T48p-PadH14)") (class "Default")
      (node (ref "IC8") (pin "H14") (pinfunction "IO,_DIFFIO_T48p_H14") (pintype "bidirectional+no_connect"))
    )
    (net (code "124") (name "unconnected-(IC8G-IO,_DIFFIO_T50p-PadG16)") (class "Default")
      (node (ref "IC8") (pin "G16") (pinfunction "IO,_DIFFIO_T50p_G16") (pintype "bidirectional+no_connect"))
    )
    (net (code "125") (name "unconnected-(IC8G-IO,_PLL2_CLKOUTn-PadA20)") (class "Default")
      (node (ref "IC8") (pin "A20") (pinfunction "IO,_PLL2_CLKOUTn_A20") (pintype "bidirectional+no_connect"))
    )
    (net (code "126") (name "unconnected-(IC8H-IO,_DIFFIO_T1n,_(DM3T{slash}BWS#3T){slash}(DM3T{slash}BWS#3T){slash}(DM5T{slash}BWS#5T)-PadF7)") (class "Default")
      (node (ref "IC8") (pin "F7") (pinfunction "IO,_DIFFIO_T1n,_(DM3T/BWS#3T)/(DM3T/BWS#3T)/(DM5T/BWS#5T)_F7") (pintype "bidirectional+no_connect"))
    )
    (net (code "127") (name "unconnected-(IC8H-IO,_DIFFIO_T1p-PadG7)") (class "Default")
      (node (ref "IC8") (pin "G7") (pinfunction "IO,_DIFFIO_T1p_G7") (pintype "bidirectional+no_connect"))
    )
    (net (code "128") (name "unconnected-(IC8H-IO,_DIFFIO_T5n,_(DATA9),_(DQ3T){slash}(DQ3T){slash}(DQ5T)-PadF8)") (class "Default")
      (node (ref "IC8") (pin "F8") (pinfunction "IO,_DIFFIO_T5n,_(DATA9),_(DQ3T)/(DQ3T)/(DQ5T)_F8") (pintype "bidirectional+no_connect"))
    )
    (net (code "129") (name "unconnected-(IC8H-IO,_DIFFIO_T5p-PadG8)") (class "Default")
      (node (ref "IC8") (pin "G8") (pinfunction "IO,_DIFFIO_T5p_G8") (pintype "bidirectional+no_connect"))
    )
    (net (code "130") (name "unconnected-(IC8H-IO,_DIFFIO_T8n-PadG10)") (class "Default")
      (node (ref "IC8") (pin "G10") (pinfunction "IO,_DIFFIO_T8n_G10") (pintype "bidirectional+no_connect"))
    )
    (net (code "131") (name "unconnected-(IC8H-IO,_DIFFIO_T8p,_(DATA6),_(DQ3T){slash}(DQ3T){slash}(DQ5T)-PadF10)") (class "Default")
      (node (ref "IC8") (pin "F10") (pinfunction "IO,_DIFFIO_T8p,_(DATA6),_(DQ3T)/(DQ3T)/(DQ5T)_F10") (pintype "bidirectional+no_connect"))
    )
    (net (code "132") (name "unconnected-(IC8H-IO,_DIFFIO_T14p-PadH10)") (class "Default")
      (node (ref "IC8") (pin "H10") (pinfunction "IO,_DIFFIO_T14p_H10") (pintype "bidirectional+no_connect"))
    )
    (net (code "133") (name "unconnected-(IC8H-IO,_DIFFIO_T22n-PadG11)") (class "Default")
      (node (ref "IC8") (pin "G11") (pinfunction "IO,_DIFFIO_T22n_G11") (pintype "bidirectional+no_connect"))
    )
    (net (code "134") (name "unconnected-(IC8H-IO,_DIFFIO_T26p-PadE10)") (class "Default")
      (node (ref "IC8") (pin "E10") (pinfunction "IO,_DIFFIO_T26p_E10") (pintype "bidirectional+no_connect"))
    )
    (net (code "135") (name "unconnected-(IC8H-IO-PadE7)") (class "Default")
      (node (ref "IC8") (pin "E7") (pinfunction "IO_E7") (pintype "bidirectional+no_connect"))
    )
    (net (code "136") (name "unconnected-(IC8H-IO-PadF9)") (class "Default")
      (node (ref "IC8") (pin "F9") (pinfunction "IO_F9") (pintype "bidirectional+no_connect"))
    )
    (net (code "137") (name "unconnected-(IC8H-IO-PadG9)") (class "Default")
      (node (ref "IC8") (pin "G9") (pinfunction "IO_G9") (pintype "bidirectional+no_connect"))
    )
  )
)
